# payment.net
KiCad netlist of a schematic drawn in Altium Designer
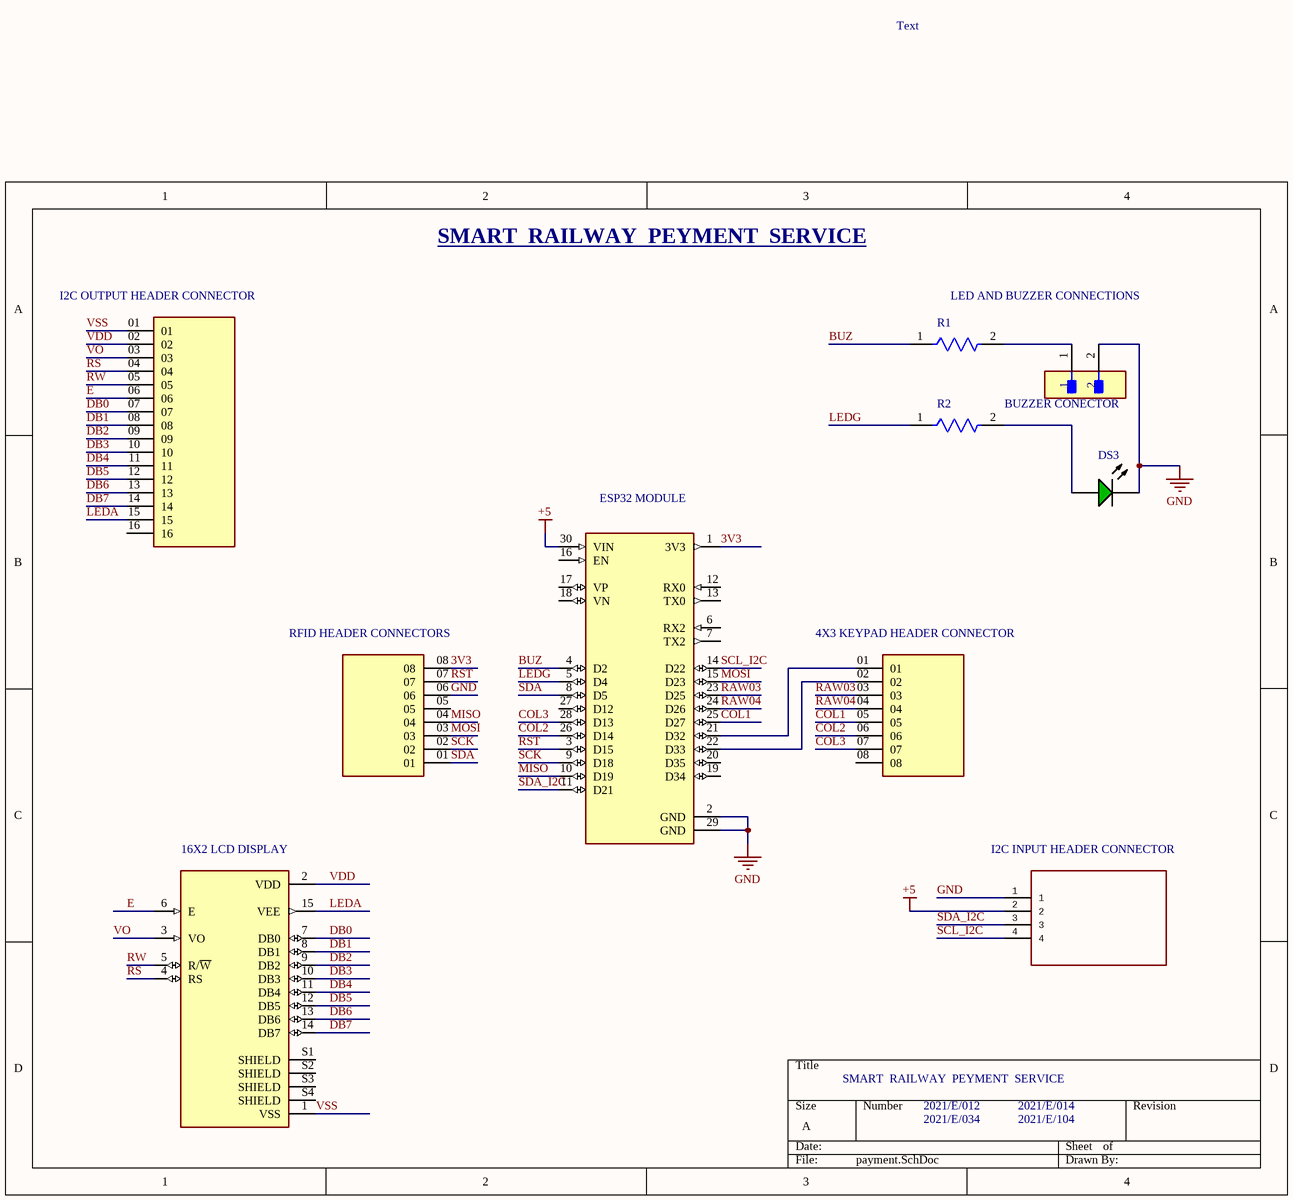
[diagram p0: payment.SchDoc]

(export (version "E")
  (design (tool "Eeschema 10.0.6"))
  (components
    (comp (ref "BUZZER CONECTOR")
      (value "M20-9990246")
      (footprint "FP-M20-9990246-MFG")
      (description "Connector Header Through Hole 2 position 0.100\" (2.54mm)")
      (fields (field (name "OCTOPART") "https://octopart.com/m20-9990246-harwin-2590635"))
      (libsource (lib "Altium Content Vault") (part "3bc925449376181038e59eaffc5286c"))
    )
    (comp (ref "DS3")
      (value "WP7113SGC")
      (footprint "KING-WP7113SGC_V")
      (description "The Super Bright Green Source Color Device, 2.2 V, -40 to 85 degC, 2-Pin THD, RoHS, Tape and Reel")
      (fields (field (name "MANUFACTURER") "Kingbright"))
      (libsource (lib "Dinumi Yashodara") (part "LED-GREEN-AK-2"))
    )
    (comp (ref "DSI")
      (value "RC1602B-BIW-CSV")
      (footprint "LCD_RC1602B-BIW-CSV")
      (description "Display: LCD; alphanumeric; STN Negative; 16x2; blue; LED; PIN: 16")
      (fields (field (name "MF") "Raystar"))
      (libsource (lib "RC1602B-BIW-CSV") (part "RC1602B-BIW-CSV"))
    )
    (comp (ref "I2C")
      (value "TSW-116-13-G-S")
      (footprint "SAMTEC_TSW-116-13-G-S")
      (libsource (lib "TSW-116-13-G-S") (part "TSW-116-13-G-S"))
    )
    (comp (ref "K-4X3")
      (value "MTSW-108-08-T-S-285")
      (footprint "SAMTEC_MTSW-108-08-T-S-285")
      (libsource (lib "") (part "MTSW-108-08-T-S-285_1"))
    )
    (comp (ref "R1")
      (value "MRS25000C1001FCT00")
      (footprint "FP-MRS25-MFG")
      (description "RES 1K OHM 0.6W 1% AXIAL")
      (fields (field (name "TOLERANCE") "1%"))
      (libsource (lib "Altium Content Vault") (part "1029c3af85768c4190bb7ad29bc67b5"))
    )
    (comp (ref "R2")
      (value "MRS25000C1001FCT00")
      (footprint "FP-MRS25-MFG")
      (description "RES 1K OHM 0.6W 1% AXIAL")
      (fields (field (name "TOLERANCE") "1%"))
      (libsource (lib "Altium Content Vault") (part "1029c3af85768c4190bb7ad29bc67b5"))
    )
    (comp (ref "RFID")
      (value "MTSW-108-08-T-S-285")
      (footprint "SAMTEC_MTSW-108-08-T-S-285")
      (libsource (lib "MTSW-108-08-T-S-285") (part "MTSW-108-08-T-S-285"))
    )
    (comp (ref "SERIAL")
      (value "SAMTEC-HTSW-104-20-X-SJ")
      (footprint "SAMTEC-HTSW-104-20-X-S")
      (libsource (lib "SAMTEC-HTSW-104-20-X-S") (part "SAMTEC-HTSW-104-20-X-SJ"))
    )
    (comp (ref "U1")
      (value "ESP32-DEVKIT-V1")
      (footprint "MODULE_ESP32_DEVKIT_V1")
      (fields (field (name "MF") "Do it"))
      (libsource (lib "ESP32-DEVKIT-V1") (part "ESP32-DEVKIT-V1"))
    )
  )
  (nets
    (net (code "1") (name "+5") (class "Default")
      (node (ref "SERIAL") (pin "2") (pinfunction "2_2") (pintype "passive"))
      (node (ref "U1") (pin "30") (pinfunction "VIN_30") (pintype "input"))
    )
    (net (code "2") (name "/3V3") (class "Default")
      (node (ref "RFID") (pin "08") (pinfunction "08_08") (pintype "passive"))
      (node (ref "U1") (pin "1") (pinfunction "3V3_1") (pintype "output"))
    )
    (net (code "3") (name "/BUZ") (class "Default")
      (node (ref "R1") (pin "1") (pinfunction "1_1") (pintype "passive"))
      (node (ref "U1") (pin "4") (pinfunction "D2_4") (pintype "bidirectional"))
    )
    (net (code "4") (name "/COL1") (class "Default")
      (node (ref "K-4X3") (pin "05") (pinfunction "05_05") (pintype "passive"))
      (node (ref "U1") (pin "25") (pinfunction "D27_25") (pintype "bidirectional"))
    )
    (net (code "5") (name "/COL2") (class "Default")
      (node (ref "K-4X3") (pin "06") (pinfunction "06_06") (pintype "passive"))
      (node (ref "U1") (pin "26") (pinfunction "D14_26") (pintype "bidirectional"))
    )
    (net (code "6") (name "/COL3") (class "Default")
      (node (ref "K-4X3") (pin "07") (pinfunction "07_07") (pintype "passive"))
      (node (ref "U1") (pin "28") (pinfunction "D13_28") (pintype "bidirectional"))
    )
    (net (code "7") (name "/DB0") (class "Default")
      (node (ref "DSI") (pin "7") (pinfunction "DB0_7") (pintype "bidirectional"))
      (node (ref "I2C") (pin "07") (pinfunction "07_07") (pintype "passive"))
    )
    (net (code "8") (name "/DB1") (class "Default")
      (node (ref "DSI") (pin "8") (pinfunction "DB1_8") (pintype "bidirectional"))
      (node (ref "I2C") (pin "08") (pinfunction "08_08") (pintype "passive"))
    )
    (net (code "9") (name "/DB2") (class "Default")
      (node (ref "DSI") (pin "9") (pinfunction "DB2_9") (pintype "bidirectional"))
      (node (ref "I2C") (pin "09") (pinfunction "09_09") (pintype "passive"))
    )
    (net (code "10") (name "/DB3") (class "Default")
      (node (ref "DSI") (pin "10") (pinfunction "DB3_10") (pintype "bidirectional"))
      (node (ref "I2C") (pin "10") (pinfunction "10_10") (pintype "passive"))
    )
    (net (code "11") (name "/DB4") (class "Default")
      (node (ref "DSI") (pin "11") (pinfunction "DB4_11") (pintype "bidirectional"))
      (node (ref "I2C") (pin "11") (pinfunction "11_11") (pintype "passive"))
    )
    (net (code "12") (name "/DB5") (class "Default")
      (node (ref "DSI") (pin "12") (pinfunction "DB5_12") (pintype "bidirectional"))
      (node (ref "I2C") (pin "12") (pinfunction "12_12") (pintype "passive"))
    )
    (net (code "13") (name "/DB6") (class "Default")
      (node (ref "DSI") (pin "13") (pinfunction "DB6_13") (pintype "bidirectional"))
      (node (ref "I2C") (pin "13") (pinfunction "13_13") (pintype "passive"))
    )
    (net (code "14") (name "/DB7") (class "Default")
      (node (ref "DSI") (pin "14") (pinfunction "DB7_14") (pintype "bidirectional"))
      (node (ref "I2C") (pin "14") (pinfunction "14_14") (pintype "passive"))
    )
    (net (code "15") (name "/E") (class "Default")
      (node (ref "DSI") (pin "6") (pinfunction "E_6") (pintype "input"))
      (node (ref "I2C") (pin "06") (pinfunction "06_06") (pintype "passive"))
    )
    (net (code "16") (name "/LEDA") (class "Default")
      (node (ref "DSI") (pin "15") (pinfunction "VEE_15") (pintype "output"))
      (node (ref "I2C") (pin "15") (pinfunction "15_15") (pintype "passive"))
    )
    (net (code "17") (name "/LEDG") (class "Default")
      (node (ref "R2") (pin "1") (pinfunction "1_1") (pintype "passive"))
      (node (ref "U1") (pin "5") (pinfunction "D4_5") (pintype "bidirectional"))
    )
    (net (code "18") (name "/MISO") (class "Default")
      (node (ref "RFID") (pin "04") (pinfunction "04_04") (pintype "passive"))
      (node (ref "U1") (pin "10") (pinfunction "D19_10") (pintype "bidirectional"))
    )
    (net (code "19") (name "/MOSI") (class "Default")
      (node (ref "RFID") (pin "03") (pinfunction "03_03") (pintype "passive"))
      (node (ref "U1") (pin "15") (pinfunction "D23_15") (pintype "bidirectional"))
    )
    (net (code "20") (name "/RAW03") (class "Default")
      (node (ref "K-4X3") (pin "03") (pinfunction "03_03") (pintype "passive"))
      (node (ref "U1") (pin "23") (pinfunction "D25_23") (pintype "bidirectional"))
    )
    (net (code "21") (name "/RAW04") (class "Default")
      (node (ref "K-4X3") (pin "04") (pinfunction "04_04") (pintype "passive"))
      (node (ref "U1") (pin "24") (pinfunction "D26_24") (pintype "bidirectional"))
    )
    (net (code "22") (name "/RS") (class "Default")
      (node (ref "DSI") (pin "4") (pinfunction "RS_4") (pintype "bidirectional"))
      (node (ref "I2C") (pin "04") (pinfunction "04_04") (pintype "passive"))
    )
    (net (code "23") (name "/RST") (class "Default")
      (node (ref "RFID") (pin "07") (pinfunction "07_07") (pintype "passive"))
      (node (ref "U1") (pin "3") (pinfunction "D15_3") (pintype "bidirectional"))
    )
    (net (code "24") (name "/RW") (class "Default")
      (node (ref "DSI") (pin "5") (pinfunction "R/~{W}_5") (pintype "bidirectional"))
      (node (ref "I2C") (pin "05") (pinfunction "05_05") (pintype "passive"))
    )
    (net (code "25") (name "/SCK") (class "Default")
      (node (ref "RFID") (pin "02") (pinfunction "02_02") (pintype "passive"))
      (node (ref "U1") (pin "9") (pinfunction "D18_9") (pintype "bidirectional"))
    )
    (net (code "26") (name "/SCL_I2C") (class "Default")
      (node (ref "SERIAL") (pin "4") (pinfunction "4_4") (pintype "passive"))
      (node (ref "U1") (pin "14") (pinfunction "D22_14") (pintype "bidirectional"))
    )
    (net (code "27") (name "/SDA") (class "Default")
      (node (ref "RFID") (pin "01") (pinfunction "01_01") (pintype "passive"))
      (node (ref "U1") (pin "8") (pinfunction "D5_8") (pintype "bidirectional"))
    )
    (net (code "28") (name "/SDA_I2C") (class "Default")
      (node (ref "SERIAL") (pin "3") (pinfunction "3_3") (pintype "passive"))
      (node (ref "U1") (pin "11") (pinfunction "D21_11") (pintype "bidirectional"))
    )
    (net (code "29") (name "/VDD") (class "Default")
      (node (ref "DSI") (pin "2") (pinfunction "VDD_2") (pintype "power_in"))
      (node (ref "I2C") (pin "02") (pinfunction "02_02") (pintype "passive"))
    )
    (net (code "30") (name "/VO") (class "Default")
      (node (ref "DSI") (pin "3") (pinfunction "VO_3") (pintype "input"))
      (node (ref "I2C") (pin "03") (pinfunction "03_03") (pintype "passive"))
    )
    (net (code "31") (name "/VSS") (class "Default")
      (node (ref "DSI") (pin "1") (pinfunction "VSS_1") (pintype "power_in"))
      (node (ref "I2C") (pin "01") (pinfunction "01_01") (pintype "passive"))
    )
    (net (code "32") (name "GND") (class "Default")
      (node (ref "BUZZER CONECTOR") (pin "2") (pinfunction "2_2") (pintype "passive"))
      (node (ref "DS3") (pin "2") (pinfunction "K_2") (pintype "passive"))
      (node (ref "RFID") (pin "06") (pinfunction "06_06") (pintype "passive"))
      (node (ref "SERIAL") (pin "1") (pinfunction "1_1") (pintype "passive"))
      (node (ref "U1") (pin "2") (pinfunction "GND_2") (pintype "power_in"))
      (node (ref "U1") (pin "29") (pinfunction "GND_29") (pintype "power_in"))
    )
    (net (code "33") (name "Net-(BUZZER CONECTOR-Pad1)") (class "Default")
      (node (ref "BUZZER CONECTOR") (pin "1") (pinfunction "1_1") (pintype "passive"))
      (node (ref "R1") (pin "2") (pinfunction "2_2") (pintype "passive"))
    )
    (net (code "34") (name "Net-(DS3-A)") (class "Default")
      (node (ref "DS3") (pin "1") (pinfunction "A_1") (pintype "passive"))
      (node (ref "R2") (pin "2") (pinfunction "2_2") (pintype "passive"))
    )
    (net (code "35") (name "Net-(U1-D32)") (class "Default")
      (node (ref "K-4X3") (pin "01") (pinfunction "01_01") (pintype "passive"))
      (node (ref "U1") (pin "21") (pinfunction "D32_21") (pintype "bidirectional"))
    )
    (net (code "36") (name "Net-(U1-D33)") (class "Default")
      (node (ref "K-4X3") (pin "02") (pinfunction "02_02") (pintype "passive"))
      (node (ref "U1") (pin "22") (pinfunction "D33_22") (pintype "bidirectional"))
    )
    (net (code "37") (name "unconnected-(DSI-SHIELD-PadS1)") (class "Default")
      (node (ref "DSI") (pin "S1") (pinfunction "SHIELD_S1") (pintype "passive"))
    )
    (net (code "38") (name "unconnected-(DSI-SHIELD-PadS2)") (class "Default")
      (node (ref "DSI") (pin "S2") (pinfunction "SHIELD_S2") (pintype "passive"))
    )
    (net (code "39") (name "unconnected-(DSI-SHIELD-PadS3)") (class "Default")
      (node (ref "DSI") (pin "S3") (pinfunction "SHIELD_S3") (pintype "passive"))
    )
    (net (code "40") (name "unconnected-(DSI-SHIELD-PadS4)") (class "Default")
      (node (ref "DSI") (pin "S4") (pinfunction "SHIELD_S4") (pintype "passive"))
    )
    (net (code "41") (name "unconnected-(I2C-Pad16)") (class "Default")
      (node (ref "I2C") (pin "16") (pinfunction "16_16") (pintype "passive"))
    )
    (net (code "42") (name "unconnected-(K-4X3-Pad08)") (class "Default")
      (node (ref "K-4X3") (pin "08") (pinfunction "08_08") (pintype "passive"))
    )
    (net (code "43") (name "unconnected-(RFID-Pad05)") (class "Default")
      (node (ref "RFID") (pin "05") (pinfunction "05_05") (pintype "passive"))
    )
    (net (code "44") (name "unconnected-(U1-D12-Pad27)") (class "Default")
      (node (ref "U1") (pin "27") (pinfunction "D12_27") (pintype "bidirectional"))
    )
    (net (code "45") (name "unconnected-(U1-D34-Pad19)") (class "Default")
      (node (ref "U1") (pin "19") (pinfunction "D34_19") (pintype "bidirectional"))
    )
    (net (code "46") (name "unconnected-(U1-D35-Pad20)") (class "Default")
      (node (ref "U1") (pin "20") (pinfunction "D35_20") (pintype "bidirectional"))
    )
    (net (code "47") (name "unconnected-(U1-EN-Pad16)") (class "Default")
      (node (ref "U1") (pin "16") (pinfunction "EN_16") (pintype "input"))
    )
    (net (code "48") (name "unconnected-(U1-RX0-Pad12)") (class "Default")
      (node (ref "U1") (pin "12") (pinfunction "RX0_12") (pintype "input"))
    )
    (net (code "49") (name "unconnected-(U1-RX2-Pad6)") (class "Default")
      (node (ref "U1") (pin "6") (pinfunction "RX2_6") (pintype "input"))
    )
    (net (code "50") (name "unconnected-(U1-TX0-Pad13)") (class "Default")
      (node (ref "U1") (pin "13") (pinfunction "TX0_13") (pintype "output"))
    )
    (net (code "51") (name "unconnected-(U1-TX2-Pad7)") (class "Default")
      (node (ref "U1") (pin "7") (pinfunction "TX2_7") (pintype "output"))
    )
    (net (code "52") (name "unconnected-(U1-VN-Pad18)") (class "Default")
      (node (ref "U1") (pin "18") (pinfunction "VN_18") (pintype "bidirectional"))
    )
    (net (code "53") (name "unconnected-(U1-VP-Pad17)") (class "Default")
      (node (ref "U1") (pin "17") (pinfunction "VP_17") (pintype "bidirectional"))
    )
  )
)
